# USB_to_SATA_bridge.net
KiCad netlist of a schematic drawn in Altium Designer
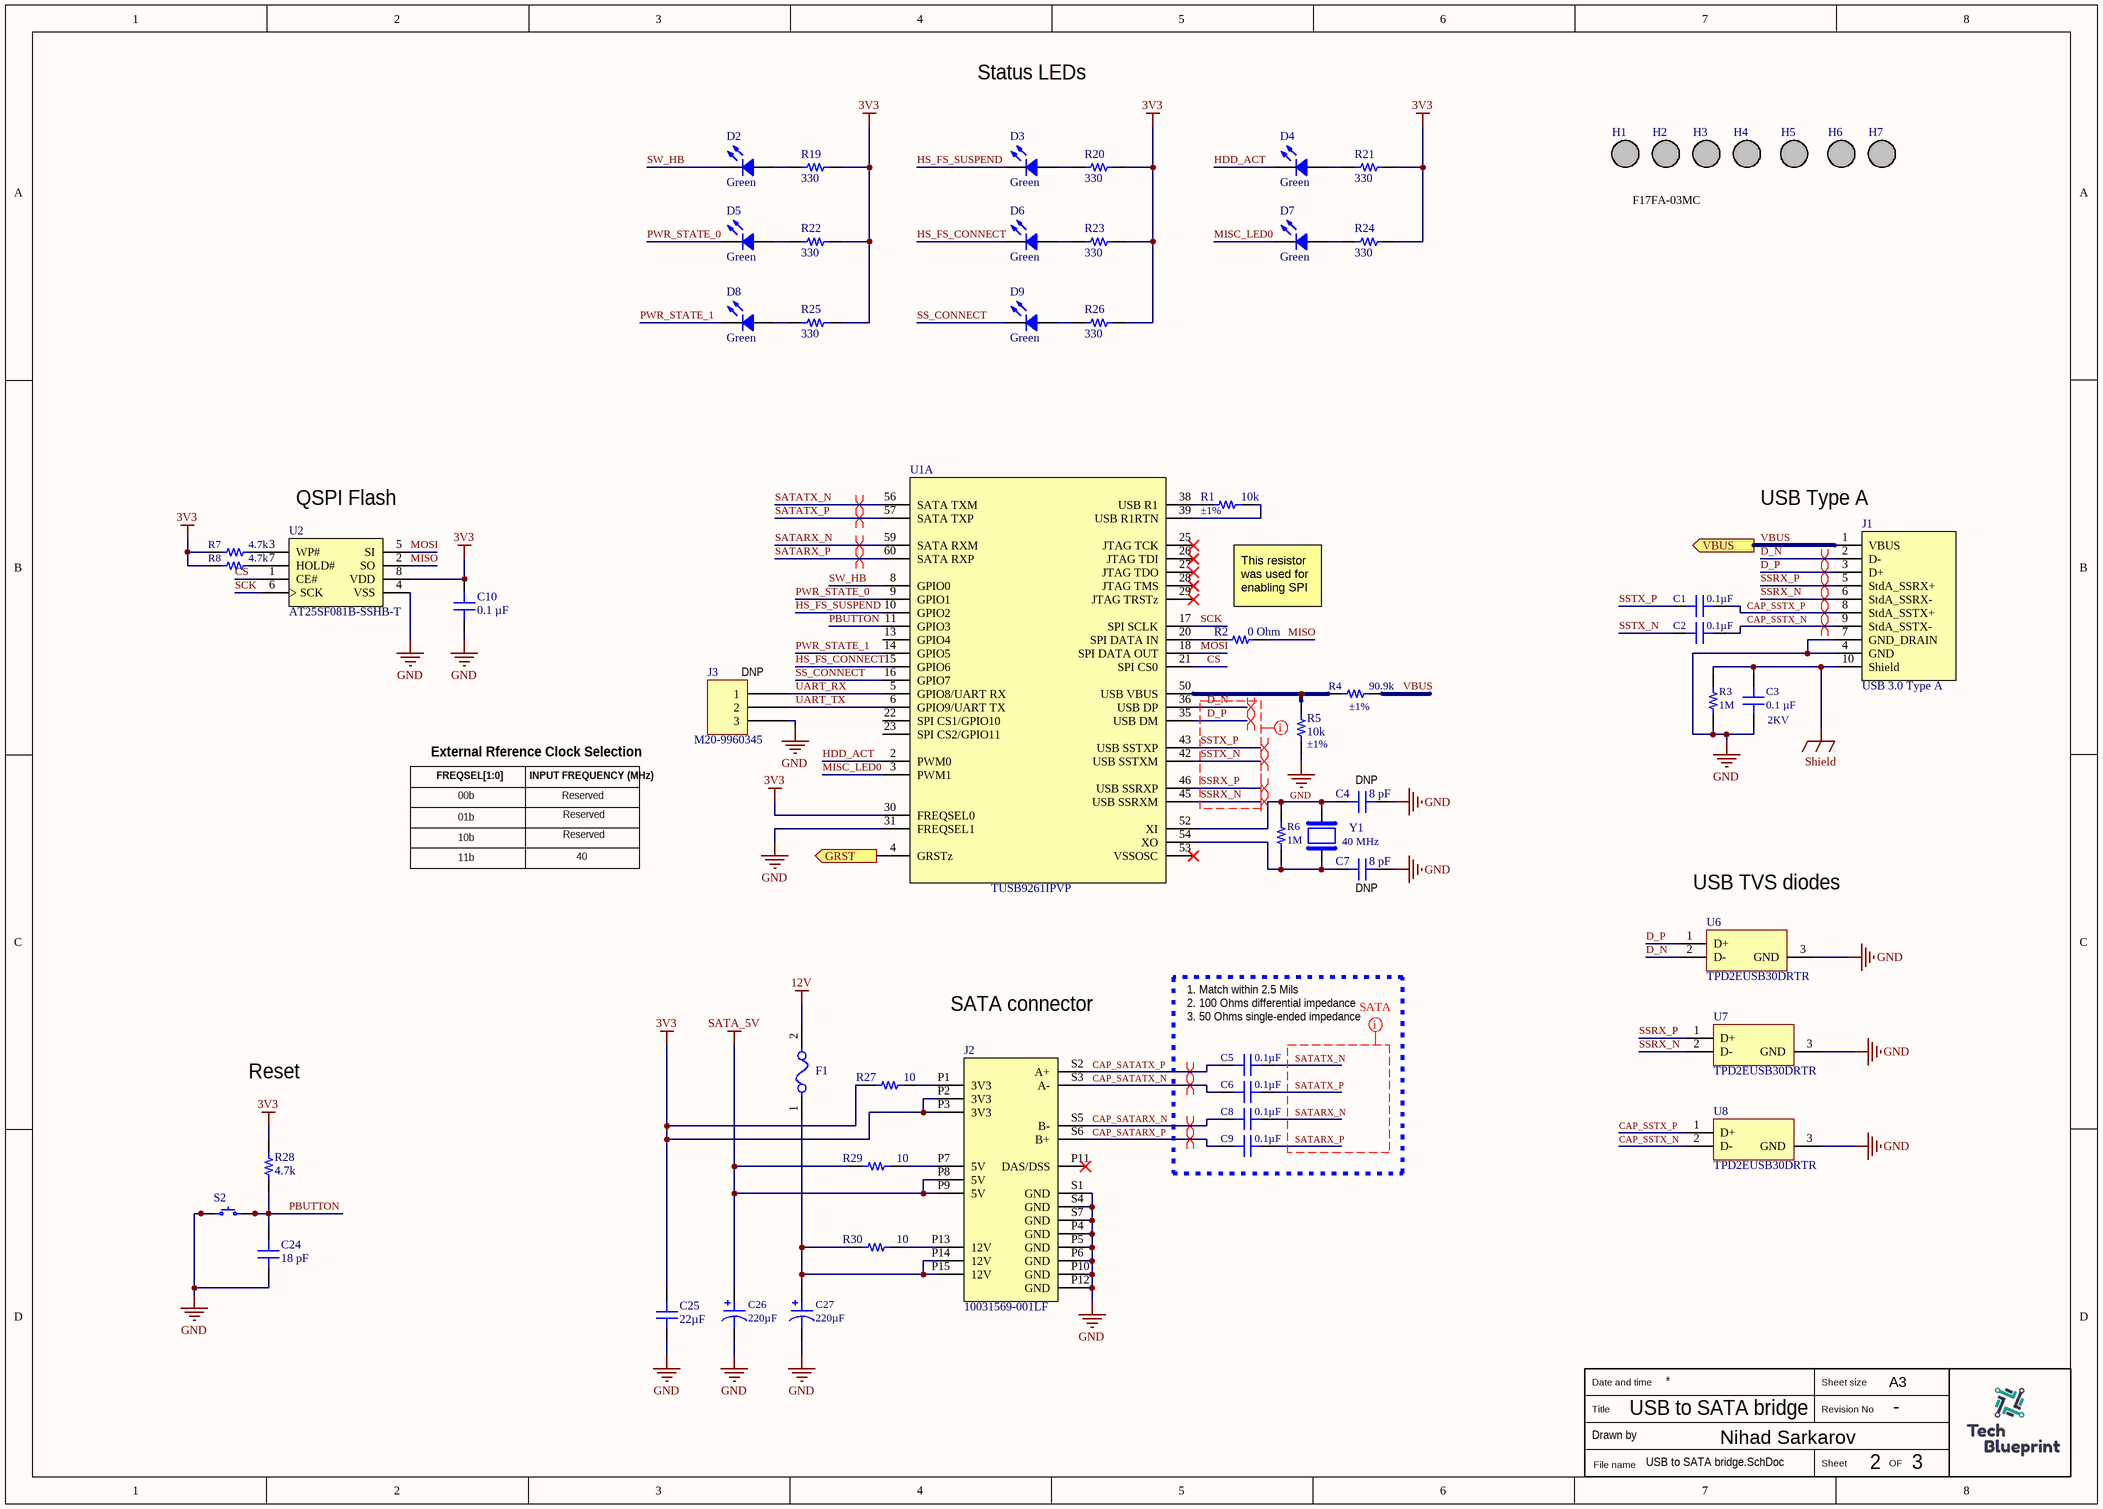
[diagram p0: USB to SATA bridge.SchDoc]

(export (version "E")
  (design (tool "Eeschema 10.0.6"))
  (components
    (comp (ref "C1")
      (value "0.1µF")
      (footprint "CAP 0402_1005")
      (description "CAP CER 0.1UF 16V X7R 0402")
      (fields
        (field (name "PART NUMBER") "0402YC104JAT4A")
        (field (name "CAPACITANCE") "0.1µF")
        (field (name "MANUFACTURER") "AVX Corporation")
      )
      (libsource (lib "Celestial Altium Library - altium_library") (part "Capacitor"))
    )
    (comp (ref "C2")
      (value "0.1µF")
      (footprint "CAP 0402_1005")
      (description "CAP CER 0.1UF 16V X7R 0402")
      (fields
        (field (name "PART NUMBER") "0402YC104JAT4A")
        (field (name "CAPACITANCE") "0.1µF")
        (field (name "MANUFACTURER") "AVX Corporation")
      )
      (libsource (lib "Celestial Altium Library - altium_library") (part "Capacitor"))
    )
    (comp (ref "C3")
      (value "0.1 µF")
      (footprint "MURATA GRM155 0402_1005")
      (description "CAP CER 0.1UF 100V X5R 0402")
      (fields
        (field (name "PART NUMBER") "GRM155R62A104ME14D")
        (field (name "CAPACITANCE") "0.1 µF")
        (field (name "MANUFACTURER") "Murata Electronics")
        (field (name "VOLTAGE - RATED") "2KV")
      )
      (libsource (lib "Celestial Altium Library - altium_library") (part "Capacitor"))
    )
    (comp (ref "C4")
      (value "8 pF")
      (footprint "MURATA GCM155 0402_1005")
      (description "CAP CER 8PF 50V C0G/NP0 0402")
      (fields
        (field (name "PART NUMBER") "GCM1555C1H8R0DA16D")
        (field (name "CAPACITANCE") "8 pF")
        (field (name "MANUFACTURER") "Murata Electronics")
      )
      (libsource (lib "Celestial Altium Library - altium_library") (part "Capacitor"))
    )
    (comp (ref "C5")
      (value "0.1µF")
      (footprint "CAP 0402_1005")
      (description "CAP CER 0.1UF 16V X7R 0402")
      (fields
        (field (name "PART NUMBER") "0402YC104JAT4A")
        (field (name "CAPACITANCE") "0.1µF")
        (field (name "MANUFACTURER") "AVX Corporation")
      )
      (libsource (lib "Celestial Altium Library - altium_library") (part "Capacitor"))
    )
    (comp (ref "C6")
      (value "0.1µF")
      (footprint "CAP 0402_1005")
      (description "CAP CER 0.1UF 16V X7R 0402")
      (fields
        (field (name "PART NUMBER") "0402YC104JAT4A")
        (field (name "CAPACITANCE") "0.1µF")
        (field (name "MANUFACTURER") "AVX Corporation")
      )
      (libsource (lib "Celestial Altium Library - altium_library") (part "Capacitor"))
    )
    (comp (ref "C7")
      (value "8 pF")
      (footprint "MURATA GCM155 0402_1005")
      (description "CAP CER 8PF 50V C0G/NP0 0402")
      (fields
        (field (name "PART NUMBER") "GCM1555C1H8R0DA16D")
        (field (name "CAPACITANCE") "8 pF")
        (field (name "MANUFACTURER") "Murata Electronics")
      )
      (libsource (lib "Celestial Altium Library - altium_library") (part "Capacitor"))
    )
    (comp (ref "C8")
      (value "0.1µF")
      (footprint "CAP 0402_1005")
      (description "CAP CER 0.1UF 16V X7R 0402")
      (fields
        (field (name "PART NUMBER") "0402YC104JAT4A")
        (field (name "CAPACITANCE") "0.1µF")
        (field (name "MANUFACTURER") "AVX Corporation")
      )
      (libsource (lib "Celestial Altium Library - altium_library") (part "Capacitor"))
    )
    (comp (ref "C9")
      (value "0.1µF")
      (footprint "CAP 0402_1005")
      (description "CAP CER 0.1UF 16V X7R 0402")
      (fields
        (field (name "PART NUMBER") "0402YC104JAT4A")
        (field (name "CAPACITANCE") "0.1µF")
        (field (name "MANUFACTURER") "AVX Corporation")
      )
      (libsource (lib "Celestial Altium Library - altium_library") (part "Capacitor"))
    )
    (comp (ref "C10")
      (value "0.1 µF")
      (footprint "CAP 0603_1608")
      (description "CAP CER 0.1UF 50V X7R 0603")
      (fields
        (field (name "PART NUMBER") "CL10B104KB85PND")
        (field (name "CAPACITANCE") "0.1 µF")
        (field (name "MANUFACTURER") "Samsung Electro-Mechanics")
      )
      (libsource (lib "Celestial Altium Library - altium_library") (part "Capacitor"))
    )
    (comp (ref "C24")
      (value "18 pF")
      (footprint "CAP 0402_1005")
      (description "CAP CER 18PF 50V C0G 0402")
      (fields
        (field (name "PART NUMBER") "CGA2B2C0G1H180J050BA")
        (field (name "CAPACITANCE") "18 pF")
        (field (name "MANUFACTURER") "TDK Corporation")
      )
      (libsource (lib "Celestial Altium Library - altium_library") (part "Capacitor"))
    )
    (comp (ref "C25")
      (value "22µF")
      (footprint "CAP 1206_3216 - 1.8MM")
      (description "CAP CER 22UF 16V X5R 1206")
      (fields
        (field (name "PART NUMBER") "1206YD226KAT2A")
        (field (name "CAPACITANCE") "22µF")
        (field (name "MANUFACTURER") "AVX Corporation")
      )
      (libsource (lib "Celestial Altium Library - altium_library") (part "Capacitor"))
    )
    (comp (ref "C26")
      (value "220µF")
      (footprint "CAP ALSMD 8.3MM H10.5MM")
      (description "CAP ALUM 220UF 20% 25V SMD")
      (fields (field (name "PART NUMBER") "UUR1E221MNL6GS") (field (name "MANUFACTURER") "Nichicon"))
      (libsource (lib "Celestial Altium Library - altium_library") (part "Polarised Capacitor"))
    )
    (comp (ref "C27")
      (value "220µF")
      (footprint "CAP ALSMD 8.3MM H10.5MM")
      (description "CAP ALUM 220UF 20% 25V SMD")
      (fields (field (name "PART NUMBER") "UUR1E221MNL6GS") (field (name "MANUFACTURER") "Nichicon"))
      (libsource (lib "Celestial Altium Library - altium_library") (part "Polarised Capacitor"))
    )
    (comp (ref "D2")
      (value "Green")
      (footprint "LED 0805_2012 GREEN")
      (description "0805 LED RED 570NM DOMINANT, 565")
      (fields
        (field (name "PART NUMBER") "QBLP631-YG1-2943")
        (field (name "MANUFACTURER") "QT Brightek (QTB)")
      )
      (libsource (lib "Celestial Altium Library - altium_library") (part "LED"))
    )
    (comp (ref "D3")
      (value "Green")
      (footprint "LED 0805_2012 GREEN")
      (description "0805 LED RED 570NM DOMINANT, 565")
      (fields
        (field (name "PART NUMBER") "QBLP631-YG1-2943")
        (field (name "MANUFACTURER") "QT Brightek (QTB)")
      )
      (libsource (lib "Celestial Altium Library - altium_library") (part "LED"))
    )
    (comp (ref "D4")
      (value "Green")
      (footprint "LED 0805_2012 GREEN")
      (description "0805 LED RED 570NM DOMINANT, 565")
      (fields
        (field (name "PART NUMBER") "QBLP631-YG1-2943")
        (field (name "MANUFACTURER") "QT Brightek (QTB)")
      )
      (libsource (lib "Celestial Altium Library - altium_library") (part "LED"))
    )
    (comp (ref "D5")
      (value "Green")
      (footprint "LED 0805_2012 GREEN")
      (description "0805 LED RED 570NM DOMINANT, 565")
      (fields
        (field (name "PART NUMBER") "QBLP631-YG1-2943")
        (field (name "MANUFACTURER") "QT Brightek (QTB)")
      )
      (libsource (lib "Celestial Altium Library - altium_library") (part "LED"))
    )
    (comp (ref "D6")
      (value "Green")
      (footprint "LED 0805_2012 GREEN")
      (description "0805 LED RED 570NM DOMINANT, 565")
      (fields
        (field (name "PART NUMBER") "QBLP631-YG1-2943")
        (field (name "MANUFACTURER") "QT Brightek (QTB)")
      )
      (libsource (lib "Celestial Altium Library - altium_library") (part "LED"))
    )
    (comp (ref "D7")
      (value "Green")
      (footprint "LED 0805_2012 GREEN")
      (description "0805 LED RED 570NM DOMINANT, 565")
      (fields
        (field (name "PART NUMBER") "QBLP631-YG1-2943")
        (field (name "MANUFACTURER") "QT Brightek (QTB)")
      )
      (libsource (lib "Celestial Altium Library - altium_library") (part "LED"))
    )
    (comp (ref "D8")
      (value "Green")
      (footprint "LED 0805_2012 GREEN")
      (description "0805 LED RED 570NM DOMINANT, 565")
      (fields
        (field (name "PART NUMBER") "QBLP631-YG1-2943")
        (field (name "MANUFACTURER") "QT Brightek (QTB)")
      )
      (libsource (lib "Celestial Altium Library - altium_library") (part "LED"))
    )
    (comp (ref "D9")
      (value "Green")
      (footprint "LED 0805_2012 GREEN")
      (description "0805 LED RED 570NM DOMINANT, 565")
      (fields
        (field (name "PART NUMBER") "QBLP631-YG1-2943")
        (field (name "MANUFACTURER") "QT Brightek (QTB)")
      )
      (libsource (lib "Celestial Altium Library - altium_library") (part "LED"))
    )
    (comp (ref "F1")
      (value "MINISMDC150F/24-2")
      (footprint "FP-MINISMDC150F-MFG")
      (description "PTC RESET FUSE 24V 1.5A 1812")
      (fields
        (field (name "MANUFACTURER") "Littelfuse")
        (field (name "OCTOPART") "https://octopart.com/minismdc150f%2F24-2-littelfuse-74215024")
      )
      (libsource (lib "Altium Content Vault") (part "5bcf9b9f640e542cf0359d10258e979"))
    )
    (comp (ref "H1") (value "Hole") (footprint "Hole") (libsource (lib "USB to SATA") (part "Hole")))
    (comp (ref "H2") (value "Hole") (footprint "Hole") (libsource (lib "USB to SATA") (part "Hole")))
    (comp (ref "H3") (value "Hole") (footprint "Hole") (libsource (lib "USB to SATA") (part "Hole")))
    (comp (ref "H4")
      (value "Mounting hole")
      (footprint "Mounting hole")
      (libsource (lib "USB to SATA") (part "Mounting hole"))
    )
    (comp (ref "H5")
      (value "Mounting hole")
      (footprint "Mounting hole")
      (libsource (lib "USB to SATA") (part "Mounting hole"))
    )
    (comp (ref "H6")
      (value "Mounting hole")
      (footprint "Mounting hole")
      (libsource (lib "USB to SATA") (part "Mounting hole"))
    )
    (comp (ref "H7")
      (value "Mounting hole")
      (footprint "Mounting hole")
      (libsource (lib "USB to SATA") (part "Mounting hole"))
    )
    (comp (ref "J1")
      (value "USB 3.0 Type A")
      (footprint "USB 3.0 Type A")
      (description "USB 3.0 Type A male connector")
      (libsource (lib "USB to SATA") (part "USB 3.0 Type A"))
    )
    (comp (ref "J2")
      (value "10031569-001LF")
      (footprint "AMPHENOL_10031569-001LF")
      (fields (field (name "MF") "{'manufacturer': u'Amphenol ICC'}"))
      (libsource (lib "USB to SATA") (part "10031569-001LF"))
    )
    (comp (ref "J3")
      (value "M20-9960345")
      (footprint "HARWIN M20-9960345")
      (description "CONN HEADER R/A 3POS 2.54MM")
      (fields (field (name "MANUFACTURER") "Harwin Inc."))
      (libsource (lib "Celestial Altium Library - altium_library") (part "3 Pin"))
    )
    (comp (ref "R1")
      (value "10k")
      (footprint "YAGEO RES 0402_1005")
      (description "RES 10K OHM 1% 1/5W 0402")
      (fields
        (field (name "PART NUMBER") "SR0402FR-7T10KL")
        (field (name "MANUFACTURER") "Yageo")
        (field (name "TOLERANCE") "±1%")
      )
      (libsource (lib "Celestial Altium Library - altium_library") (part "Resistor"))
    )
    (comp (ref "R2")
      (value "0 Ohm")
      (footprint "RES 0603_1608")
      (description "RCS0603 0R0 ET6 E3")
      (fields (field (name "PART NUMBER") "RCS06030000Z0EC") (field (name "MANUFACTURER") "Vishay Dale"))
      (libsource (lib "Celestial Altium Library - altium_library") (part "Resistor"))
    )
    (comp (ref "R3")
      (value "1M")
      (footprint "RES 0603_1608")
      (description "RES 1M OHM 5% 1/10W 0603")
      (fields
        (field (name "PART NUMBER") "RMCF0603JT1M00")
        (field (name "MANUFACTURER") "Stackpole Electronics Inc")
      )
      (libsource (lib "Celestial Altium Library - altium_library") (part "Resistor"))
    )
    (comp (ref "R4")
      (value "90.9k")
      (footprint "RES 0603_1608")
      (description "RES SMD 90.9K OHM 1% 1/8W 0603")
      (fields
        (field (name "PART NUMBER") "MCT06030C9092FP500")
        (field (name "MANUFACTURER") "Vishay Beyschlag")
        (field (name "TOLERANCE") "±1%")
      )
      (libsource (lib "Celestial Altium Library - altium_library") (part "Resistor"))
    )
    (comp (ref "R5")
      (value "10k")
      (footprint "YAGEO RES 0603_1608")
      (description "RES SMD 10K OHM 1% 1/10W 0603")
      (fields
        (field (name "PART NUMBER") "RT0603FRE0710KL")
        (field (name "MANUFACTURER") "Yageo")
        (field (name "TOLERANCE") "±1%")
      )
      (libsource (lib "Celestial Altium Library - altium_library") (part "Resistor"))
    )
    (comp (ref "R6")
      (value "1M")
      (footprint "YAGEO RES 0402_1005")
      (description "RES SMD 1M OHM 5% 1/16W 0402")
      (fields (field (name "PART NUMBER") "AC0402JR-071ML") (field (name "MANUFACTURER") "Yageo"))
      (libsource (lib "Celestial Altium Library - altium_library") (part "Resistor"))
    )
    (comp (ref "R7")
      (value "4.7k")
      (footprint "RES 0603_1608")
      (description "RES 4.7K OHM 5% 1/10W 0603")
      (fields
        (field (name "PART NUMBER") "RMCF0603JT4K70")
        (field (name "MANUFACTURER") "Stackpole Electronics Inc")
      )
      (libsource (lib "Celestial Altium Library - altium_library") (part "Resistor"))
    )
    (comp (ref "R8")
      (value "4.7k")
      (footprint "RES 0603_1608")
      (description "RES 4.7K OHM 5% 1/10W 0603")
      (fields
        (field (name "PART NUMBER") "RMCF0603JT4K70")
        (field (name "MANUFACTURER") "Stackpole Electronics Inc")
      )
      (libsource (lib "Celestial Altium Library - altium_library") (part "Resistor"))
    )
    (comp (ref "R19")
      (value "330")
      (footprint "YAGEO RES 0402_1005")
      (description "RES SMD 330 OHM 5% 1/16W 0402")
      (fields (field (name "PART NUMBER") "AC0402JR-07330RL") (field (name "MANUFACTURER") "Yageo"))
      (libsource (lib "Celestial Altium Library - altium_library") (part "Resistor"))
    )
    (comp (ref "R20")
      (value "330")
      (footprint "YAGEO RES 0402_1005")
      (description "RES SMD 330 OHM 5% 1/16W 0402")
      (fields (field (name "PART NUMBER") "AC0402JR-07330RL") (field (name "MANUFACTURER") "Yageo"))
      (libsource (lib "Celestial Altium Library - altium_library") (part "Resistor"))
    )
    (comp (ref "R21")
      (value "330")
      (footprint "YAGEO RES 0402_1005")
      (description "RES SMD 330 OHM 5% 1/16W 0402")
      (fields (field (name "PART NUMBER") "AC0402JR-07330RL") (field (name "MANUFACTURER") "Yageo"))
      (libsource (lib "Celestial Altium Library - altium_library") (part "Resistor"))
    )
    (comp (ref "R22")
      (value "330")
      (footprint "YAGEO RES 0402_1005")
      (description "RES SMD 330 OHM 5% 1/16W 0402")
      (fields (field (name "PART NUMBER") "AC0402JR-07330RL") (field (name "MANUFACTURER") "Yageo"))
      (libsource (lib "Celestial Altium Library - altium_library") (part "Resistor"))
    )
    (comp (ref "R23")
      (value "330")
      (footprint "YAGEO RES 0402_1005")
      (description "RES SMD 330 OHM 5% 1/16W 0402")
      (fields (field (name "PART NUMBER") "AC0402JR-07330RL") (field (name "MANUFACTURER") "Yageo"))
      (libsource (lib "Celestial Altium Library - altium_library") (part "Resistor"))
    )
    (comp (ref "R24")
      (value "330")
      (footprint "YAGEO RES 0402_1005")
      (description "RES SMD 330 OHM 5% 1/16W 0402")
      (fields (field (name "PART NUMBER") "AC0402JR-07330RL") (field (name "MANUFACTURER") "Yageo"))
      (libsource (lib "Celestial Altium Library - altium_library") (part "Resistor"))
    )
    (comp (ref "R25")
      (value "330")
      (footprint "YAGEO RES 0402_1005")
      (description "RES SMD 330 OHM 5% 1/16W 0402")
      (fields (field (name "PART NUMBER") "AC0402JR-07330RL") (field (name "MANUFACTURER") "Yageo"))
      (libsource (lib "Celestial Altium Library - altium_library") (part "Resistor"))
    )
    (comp (ref "R26")
      (value "330")
      (footprint "YAGEO RES 0402_1005")
      (description "RES SMD 330 OHM 5% 1/16W 0402")
      (fields (field (name "PART NUMBER") "AC0402JR-07330RL") (field (name "MANUFACTURER") "Yageo"))
      (libsource (lib "Celestial Altium Library - altium_library") (part "Resistor"))
    )
    (comp (ref "R27")
      (value "10")
      (footprint "RES 1206_3216")
      (description "RCC1206 200 10R 5% ET1 E3")
      (fields (field (name "PART NUMBER") "RCC120610R0JNEA") (field (name "MANUFACTURER") "Vishay Dale"))
      (libsource (lib "Celestial Altium Library - altium_library") (part "Resistor"))
    )
    (comp (ref "R28")
      (value "4.7k")
      (footprint "YAGEO RES 0402_1005")
      (description "RES SMD 4.7K OHM 5% 1/16W 0402")
      (fields (field (name "PART NUMBER") "AC0402JR-074K7L") (field (name "MANUFACTURER") "Yageo"))
      (libsource (lib "Celestial Altium Library - altium_library") (part "Resistor"))
    )
    (comp (ref "R29")
      (value "10")
      (footprint "RES 1206_3216")
      (description "RCC1206 200 10R 5% ET1 E3")
      (fields (field (name "PART NUMBER") "RCC120610R0JNEA") (field (name "MANUFACTURER") "Vishay Dale"))
      (libsource (lib "Celestial Altium Library - altium_library") (part "Resistor"))
    )
    (comp (ref "R30")
      (value "10")
      (footprint "RES 1206_3216")
      (description "RCC1206 200 10R 5% ET1 E3")
      (fields (field (name "PART NUMBER") "RCC120610R0JNEA") (field (name "MANUFACTURER") "Vishay Dale"))
      (libsource (lib "Celestial Altium Library - altium_library") (part "Resistor"))
    )
    (comp (ref "S2")
      (value "PTS645SM43SMTR92 LFS")
      (footprint "C&K PTS645")
      (description "SWITCH TACTILE SPST-NO 0.05A 12V")
      (fields (field (name "MANUFACTURER") "C&K"))
      (libsource (lib "Celestial Altium Library - altium_library") (part "SPST-NO 4 PIN"))
    )
    (comp (ref "U1")
      (value "TUSB9261IPVP")
      (footprint "FP-PVP0064A-IPC_A")
      (description "HDD, CD, DVD Drive Interface 64-HTQFP (7x7)")
      (fields
        (field (name "MANUFACTURER") "Texas Instruments")
        (field (name "DIGIKEY PART NUMBER") "296-35545-ND")
      )
      (libsource (lib "USB to SATA") (part "TUSB9261IPVP"))
    )
    (comp (ref "U2")
      (value "AT25SF081B-SSHB-T")
      (footprint "SST25VF016B-75-4I-S2AF-T:SOIC127P790X216-8N")
      (description "FLASH - NOR Memory IC 8Mbit SPI - Quad I/O 108 MHz 8-SOIC")
      (fields
        (field (name "MF") "{'manufacturer': u'Microchip Technology'}")
        (field (name "MP") "SST25VF016B-75-4I-S2AF-T")
      )
      (libsource (lib "USB to SATA") (part "SST25VF016B-75-4I-S2AF-T"))
    )
    (comp (ref "U6")
      (value "TPD2EUSB30DRTR")
      (footprint "DRT0003A")
      (fields (field (name "MANUFACTURER") "Texas Instruments"))
      (libsource (lib "Altium Content Vault") (part "TI-TPD2EUSB30-SOT_DRT-3"))
    )
    (comp (ref "U7")
      (value "TPD2EUSB30DRTR")
      (footprint "DRT0003A")
      (fields (field (name "MANUFACTURER") "Texas Instruments"))
      (libsource (lib "Altium Content Vault") (part "TI-TPD2EUSB30-SOT_DRT-3"))
    )
    (comp (ref "U8")
      (value "TPD2EUSB30DRTR")
      (footprint "DRT0003A")
      (fields (field (name "MANUFACTURER") "Texas Instruments"))
      (libsource (lib "Altium Content Vault") (part "TI-TPD2EUSB30-SOT_DRT-3"))
    )
    (comp (ref "Y1")
      (value "SXT22412AA07-40.000M")
      (footprint "XTAL_SXT22412AA16-40.000MT")
      (description "40 MHz ±50ppm Crystal 12pF 50 Ohms 4-SMD, No Lead")
      (fields (field (name "MF") "Suntsu Electronics, Inc") (field (name "FREQUENCY") "40 MHz"))
      (libsource (lib "USB to SATA") (part "SXT22412AA07-40.000M"))
    )
  )
  (nets
    (net (code "1") (name "/CAP_SATARX_N") (class "Default")
      (node (ref "C8") (pin "1") (pinfunction "1_1") (pintype "passive"))
      (node (ref "J2") (pin "S5") (pinfunction "B-_S5") (pintype "passive"))
    )
    (net (code "2") (name "/CAP_SATARX_P") (class "Default")
      (node (ref "C9") (pin "1") (pinfunction "1_1") (pintype "passive"))
      (node (ref "J2") (pin "S6") (pinfunction "B+_S6") (pintype "passive"))
    )
    (net (code "3") (name "/CAP_SATATX_N") (class "Default")
      (node (ref "C6") (pin "1") (pinfunction "1_1") (pintype "passive"))
      (node (ref "J2") (pin "S3") (pinfunction "A-_S3") (pintype "passive"))
    )
    (net (code "4") (name "/CAP_SATATX_P") (class "Default")
      (node (ref "C5") (pin "1") (pinfunction "1_1") (pintype "passive"))
      (node (ref "J2") (pin "S2") (pinfunction "A+_S2") (pintype "passive"))
    )
    (net (code "5") (name "/CAP_SSTX_N") (class "Default")
      (node (ref "C2") (pin "2") (pinfunction "2_2") (pintype "passive"))
      (node (ref "J1") (pin "9") (pinfunction "StdA_SSTX-_9") (pintype "passive"))
      (node (ref "U8") (pin "2") (pinfunction "D-_2") (pintype "passive"))
    )
    (net (code "6") (name "/CAP_SSTX_P") (class "Default")
      (node (ref "C1") (pin "2") (pinfunction "2_2") (pintype "passive"))
      (node (ref "J1") (pin "8") (pinfunction "StdA_SSTX+_8") (pintype "passive"))
      (node (ref "U8") (pin "1") (pinfunction "D+_1") (pintype "passive"))
    )
    (net (code "7") (name "/CS") (class "Default")
      (node (ref "U1") (pin "21") (pinfunction "SPI_CS0_21") (pintype "passive"))
      (node (ref "U2") (pin "1") (pinfunction "CE#_1") (pintype "passive"))
    )
    (net (code "8") (name "/D_N") (class "Default")
      (node (ref "J1") (pin "2") (pinfunction "D-_2") (pintype "passive"))
      (node (ref "U1") (pin "36") (pinfunction "USB_DP_36") (pintype "passive"))
      (node (ref "U6") (pin "2") (pinfunction "D-_2") (pintype "passive"))
    )
    (net (code "9") (name "/D_P") (class "Default")
      (node (ref "J1") (pin "3") (pinfunction "D+_3") (pintype "passive"))
      (node (ref "U1") (pin "35") (pinfunction "USB_DM_35") (pintype "passive"))
      (node (ref "U6") (pin "1") (pinfunction "D+_1") (pintype "passive"))
    )
    (net (code "10") (name "/GRST") (class "Default")
      (node (ref "U1") (pin "4") (pinfunction "GRSTz_4") (pintype "passive"))
    )
    (net (code "11") (name "/HDD_ACT") (class "Default")
      (node (ref "D4") (pin "2") (pinfunction "2_2") (pintype "passive"))
      (node (ref "U1") (pin "2") (pinfunction "PWM0_2") (pintype "passive"))
    )
    (net (code "12") (name "/HS_FS_CONNECT") (class "Default")
      (node (ref "D6") (pin "2") (pinfunction "2_2") (pintype "passive"))
      (node (ref "U1") (pin "15") (pinfunction "GPIO6_15") (pintype "passive"))
    )
    (net (code "13") (name "/HS_FS_SUSPEND") (class "Default")
      (node (ref "D3") (pin "2") (pinfunction "2_2") (pintype "passive"))
      (node (ref "U1") (pin "10") (pinfunction "GPIO2_10") (pintype "passive"))
    )
    (net (code "14") (name "/MISC_LED0") (class "Default")
      (node (ref "D7") (pin "2") (pinfunction "2_2") (pintype "passive"))
      (node (ref "U1") (pin "3") (pinfunction "PWM1_3") (pintype "passive"))
    )
    (net (code "15") (name "/MISO") (class "Default")
      (node (ref "R2") (pin "2") (pinfunction "2_2") (pintype "passive"))
      (node (ref "U2") (pin "2") (pinfunction "SO_2") (pintype "passive"))
    )
    (net (code "16") (name "/MOSI") (class "Default")
      (node (ref "U1") (pin "18") (pinfunction "SPI_DATA_OUT_18") (pintype "passive"))
      (node (ref "U2") (pin "5") (pinfunction "SI_5") (pintype "passive"))
    )
    (net (code "17") (name "/PBUTTON") (class "Default")
      (node (ref "C24") (pin "2") (pinfunction "2_2") (pintype "passive"))
      (node (ref "R28") (pin "1") (pinfunction "1_1") (pintype "passive"))
      (node (ref "S2") (pin "3") (pinfunction "3_3") (pintype "passive"))
      (node (ref "S2") (pin "4") (pinfunction "4_4") (pintype "passive"))
      (node (ref "U1") (pin "11") (pinfunction "GPIO3_11") (pintype "passive"))
    )
    (net (code "18") (name "/PWR_STATE_0") (class "Default")
      (node (ref "D5") (pin "2") (pinfunction "2_2") (pintype "passive"))
      (node (ref "U1") (pin "9") (pinfunction "GPIO1_9") (pintype "passive"))
    )
    (net (code "19") (name "/PWR_STATE_1") (class "Default")
      (node (ref "D8") (pin "2") (pinfunction "2_2") (pintype "passive"))
      (node (ref "U1") (pin "14") (pinfunction "GPIO5_14") (pintype "passive"))
    )
    (net (code "20") (name "/SATARX_N") (class "Default")
      (node (ref "C8") (pin "2") (pinfunction "2_2") (pintype "passive"))
      (node (ref "U1") (pin "59") (pinfunction "SATA_RXM_59") (pintype "passive"))
    )
    (net (code "21") (name "/SATARX_P") (class "Default")
      (node (ref "C9") (pin "2") (pinfunction "2_2") (pintype "passive"))
      (node (ref "U1") (pin "60") (pinfunction "SATA_RXP_60") (pintype "passive"))
    )
    (net (code "22") (name "/SATATX_N") (class "Default")
      (node (ref "C5") (pin "2") (pinfunction "2_2") (pintype "passive"))
      (node (ref "U1") (pin "56") (pinfunction "SATA_TXM_56") (pintype "passive"))
    )
    (net (code "23") (name "/SATATX_P") (class "Default")
      (node (ref "C6") (pin "2") (pinfunction "2_2") (pintype "passive"))
      (node (ref "U1") (pin "57") (pinfunction "SATA_TXP_57") (pintype "passive"))
    )
    (net (code "24") (name "/SCK") (class "Default")
      (node (ref "U1") (pin "17") (pinfunction "SPI_SCLK_17") (pintype "passive"))
      (node (ref "U2") (pin "6") (pinfunction "SCK_6") (pintype "passive"))
    )
    (net (code "25") (name "/SSRX_N") (class "Default")
      (node (ref "J1") (pin "6") (pinfunction "StdA_SSRX-_6") (pintype "passive"))
      (node (ref "U1") (pin "45") (pinfunction "USB_SSRXM_45") (pintype "passive"))
      (node (ref "U7") (pin "2") (pinfunction "D-_2") (pintype "passive"))
    )
    (net (code "26") (name "/SSRX_P") (class "Default")
      (node (ref "J1") (pin "5") (pinfunction "StdA_SSRX+_5") (pintype "passive"))
      (node (ref "U1") (pin "46") (pinfunction "USB_SSRXP_46") (pintype "passive"))
      (node (ref "U7") (pin "1") (pinfunction "D+_1") (pintype "passive"))
    )
    (net (code "27") (name "/SSTX_N") (class "Default")
      (node (ref "C2") (pin "1") (pinfunction "1_1") (pintype "passive"))
      (node (ref "U1") (pin "42") (pinfunction "USB_SSTXM_42") (pintype "passive"))
    )
    (net (code "28") (name "/SSTX_P") (class "Default")
      (node (ref "C1") (pin "1") (pinfunction "1_1") (pintype "passive"))
      (node (ref "U1") (pin "43") (pinfunction "USB_SSTXP_43") (pintype "passive"))
    )
    (net (code "29") (name "/SS_CONNECT") (class "Default")
      (node (ref "D9") (pin "2") (pinfunction "2_2") (pintype "passive"))
      (node (ref "U1") (pin "16") (pinfunction "GPIO7_16") (pintype "passive"))
    )
    (net (code "30") (name "/SW_HB") (class "Default")
      (node (ref "D2") (pin "2") (pinfunction "2_2") (pintype "passive"))
      (node (ref "U1") (pin "8") (pinfunction "GPIO0_8") (pintype "passive"))
    )
    (net (code "31") (name "/UART_RX") (class "Default")
      (node (ref "J3") (pin "1") (pinfunction "1_1") (pintype "passive"))
      (node (ref "U1") (pin "5") (pinfunction "GPIO8/UART_RX_5") (pintype "passive"))
    )
    (net (code "32") (name "/UART_TX") (class "Default")
      (node (ref "J3") (pin "2") (pinfunction "2_2") (pintype "passive"))
      (node (ref "U1") (pin "6") (pinfunction "GPIO9/UART_TX_6") (pintype "passive"))
    )
    (net (code "33") (name "/VBUS") (class "Default")
      (node (ref "J1") (pin "1") (pinfunction "VBUS_1") (pintype "passive"))
      (node (ref "R4") (pin "2") (pinfunction "2_2") (pintype "passive"))
    )
    (net (code "34") (name "3V3") (class "Default")
      (node (ref "C10") (pin "2") (pinfunction "2_2") (pintype "passive"))
      (node (ref "C25") (pin "2") (pinfunction "2_2") (pintype "passive"))
      (node (ref "J2") (pin "P2") (pinfunction "3V3_P2") (pintype "passive"))
      (node (ref "J2") (pin "P3") (pinfunction "3V3_P3") (pintype "passive"))
      (node (ref "R19") (pin "2") (pinfunction "2_2") (pintype "passive"))
      (node (ref "R20") (pin "2") (pinfunction "2_2") (pintype "passive"))
      (node (ref "R21") (pin "2") (pinfunction "2_2") (pintype "passive"))
      (node (ref "R22") (pin "2") (pinfunction "2_2") (pintype "passive"))
      (node (ref "R23") (pin "2") (pinfunction "2_2") (pintype "passive"))
      (node (ref "R24") (pin "2") (pinfunction "2_2") (pintype "passive"))
      (node (ref "R25") (pin "2") (pinfunction "2_2") (pintype "passive"))
      (node (ref "R26") (pin "2") (pinfunction "2_2") (pintype "passive"))
      (node (ref "R27") (pin "1") (pinfunction "1_1") (pintype "passive"))
      (node (ref "R28") (pin "2") (pinfunction "2_2") (pintype "passive"))
      (node (ref "R7") (pin "1") (pinfunction "1_1") (pintype "passive"))
      (node (ref "R8") (pin "1") (pinfunction "1_1") (pintype "passive"))
      (node (ref "U1") (pin "30") (pinfunction "FREQSEL0_30") (pintype "passive"))
      (node (ref "U2") (pin "8") (pinfunction "VDD_8") (pintype "power_in"))
    )
    (net (code "35") (name "12V") (class "Default")
      (node (ref "F1") (pin "2") (pinfunction "2_2") (pintype "passive"))
    )
    (net (code "36") (name "GND") (class "Default")
      (node (ref "C10") (pin "1") (pinfunction "1_1") (pintype "passive"))
      (node (ref "C24") (pin "1") (pinfunction "1_1") (pintype "passive"))
      (node (ref "C25") (pin "1") (pinfunction "1_1") (pintype "passive"))
      (node (ref "C26") (pin "2") (pinfunction "2_2") (pintype "passive"))
      (node (ref "C27") (pin "2") (pinfunction "2_2") (pintype "passive"))
      (node (ref "C3") (pin "1") (pinfunction "1_1") (pintype "passive"))
      (node (ref "C4") (pin "2") (pinfunction "2_2") (pintype "passive"))
      (node (ref "C7") (pin "2") (pinfunction "2_2") (pintype "passive"))
      (node (ref "J1") (pin "4") (pinfunction "GND_4") (pintype "passive"))
      (node (ref "J1") (pin "7") (pinfunction "GND_DRAIN_7") (pintype "passive"))
      (node (ref "J2") (pin "P10") (pinfunction "GND_P10") (pintype "passive"))
      (node (ref "J2") (pin "P12") (pinfunction "GND_P12") (pintype "passive"))
      (node (ref "J2") (pin "P4") (pinfunction "GND_P4") (pintype "passive"))
      (node (ref "J2") (pin "P5") (pinfunction "GND_P5") (pintype "passive"))
      (node (ref "J2") (pin "P6") (pinfunction "GND_P6") (pintype "passive"))
      (node (ref "J2") (pin "S1") (pinfunction "GND_S1") (pintype "passive"))
      (node (ref "J2") (pin "S4") (pinfunction "GND_S4") (pintype "passive"))
      (node (ref "J2") (pin "S7") (pinfunction "GND_S7") (pintype "passive"))
      (node (ref "J3") (pin "3") (pinfunction "3_3") (pintype "passive"))
      (node (ref "R3") (pin "1") (pinfunction "1_1") (pintype "passive"))
      (node (ref "R5") (pin "1") (pinfunction "1_1") (pintype "passive"))
      (node (ref "S2") (pin "1") (pinfunction "1_1") (pintype "passive"))
      (node (ref "S2") (pin "2") (pinfunction "2_2") (pintype "passive"))
      (node (ref "U1") (pin "31") (pinfunction "FREQSEL1_31") (pintype "passive"))
      (node (ref "U2") (pin "4") (pinfunction "VSS_4") (pintype "power_in"))
      (node (ref "U6") (pin "3") (pinfunction "GND_3") (pintype "power_in"))
      (node (ref "U7") (pin "3") (pinfunction "GND_3") (pintype "power_in"))
      (node (ref "U8") (pin "3") (pinfunction "GND_3") (pintype "power_in"))
    )
    (net (code "37") (name "Net-(C27-Pad1)") (class "Default")
      (node (ref "C27") (pin "1") (pinfunction "1_1") (pintype "passive"))
      (node (ref "F1") (pin "1") (pinfunction "1_1") (pintype "passive"))
      (node (ref "J2") (pin "P14") (pinfunction "12V_P14") (pintype "passive"))
      (node (ref "J2") (pin "P15") (pinfunction "12V_P15") (pintype "passive"))
      (node (ref "R30") (pin "1") (pinfunction "1_1") (pintype "passive"))
    )
    (net (code "38") (name "Net-(D2-Pad1)") (class "Default")
      (node (ref "D2") (pin "1") (pinfunction "1_1") (pintype "passive"))
      (node (ref "R19") (pin "1") (pinfunction "1_1") (pintype "passive"))
    )
    (net (code "39") (name "Net-(D3-Pad1)") (class "Default")
      (node (ref "D3") (pin "1") (pinfunction "1_1") (pintype "passive"))
      (node (ref "R20") (pin "1") (pinfunction "1_1") (pintype "passive"))
    )
    (net (code "40") (name "Net-(D4-Pad1)") (class "Default")
      (node (ref "D4") (pin "1") (pinfunction "1_1") (pintype "passive"))
      (node (ref "R21") (pin "1") (pinfunction "1_1") (pintype "passive"))
    )
    (net (code "41") (name "Net-(D5-Pad1)") (class "Default")
      (node (ref "D5") (pin "1") (pinfunction "1_1") (pintype "passive"))
      (node (ref "R22") (pin "1") (pinfunction "1_1") (pintype "passive"))
    )
    (net (code "42") (name "Net-(D6-Pad1)") (class "Default")
      (node (ref "D6") (pin "1") (pinfunction "1_1") (pintype "passive"))
      (node (ref "R23") (pin "1") (pinfunction "1_1") (pintype "passive"))
    )
    (net (code "43") (name "Net-(D7-Pad1)") (class "Default")
      (node (ref "D7") (pin "1") (pinfunction "1_1") (pintype "passive"))
      (node (ref "R24") (pin "1") (pinfunction "1_1") (pintype "passive"))
    )
    (net (code "44") (name "Net-(D8-Pad1)") (class "Default")
      (node (ref "D8") (pin "1") (pinfunction "1_1") (pintype "passive"))
      (node (ref "R25") (pin "1") (pinfunction "1_1") (pintype "passive"))
    )
    (net (code "45") (name "Net-(D9-Pad1)") (class "Default")
      (node (ref "D9") (pin "1") (pinfunction "1_1") (pintype "passive"))
      (node (ref "R26") (pin "1") (pinfunction "1_1") (pintype "passive"))
    )
    (net (code "46") (name "Net-(J2-3V3-PadP1)") (class "Default")
      (node (ref "J2") (pin "P1") (pinfunction "3V3_P1") (pintype "passive"))
      (node (ref "R27") (pin "2") (pinfunction "2_2") (pintype "passive"))
    )
    (net (code "47") (name "Net-(J2-5V-PadP7)") (class "Default")
      (node (ref "J2") (pin "P7") (pinfunction "5V_P7") (pintype "passive"))
      (node (ref "R29") (pin "2") (pinfunction "2_2") (pintype "passive"))
    )
    (net (code "48") (name "Net-(J2-12V-PadP13)") (class "Default")
      (node (ref "J2") (pin "P13") (pinfunction "12V_P13") (pintype "passive"))
      (node (ref "R30") (pin "2") (pinfunction "2_2") (pintype "passive"))
    )
    (net (code "49") (name "Net-(U1A-SPI_DATA_IN)") (class "Default")
      (node (ref "R2") (pin "1") (pinfunction "1_1") (pintype "passive"))
      (node (ref "U1") (pin "20") (pinfunction "SPI_DATA_IN_20") (pintype "passive"))
    )
    (net (code "50") (name "Net-(U1A-USB_R1)") (class "Default")
      (node (ref "R1") (pin "1") (pinfunction "1_1") (pintype "passive"))
      (node (ref "U1") (pin "38") (pinfunction "USB_R1_38") (pintype "passive"))
    )
    (net (code "51") (name "Net-(U1A-USB_R1RTN)") (class "Default")
      (node (ref "R1") (pin "2") (pinfunction "2_2") (pintype "passive"))
      (node (ref "U1") (pin "39") (pinfunction "USB_R1RTN_39") (pintype "passive"))
    )
    (net (code "52") (name "Net-(U1A-USB_VBUS)") (class "Default")
      (node (ref "R4") (pin "1") (pinfunction "1_1") (pintype "passive"))
      (node (ref "R5") (pin "2") (pinfunction "2_2") (pintype "passive"))
      (node (ref "U1") (pin "50") (pinfunction "USB_VBUS_50") (pintype "passive"))
    )
    (net (code "53") (name "Net-(U1A-XI)") (class "Default")
      (node (ref "C4") (pin "1") (pinfunction "1_1") (pintype "passive"))
      (node (ref "R6") (pin "2") (pinfunction "2_2") (pintype "passive"))
      (node (ref "U1") (pin "52") (pinfunction "XI_52") (pintype "passive"))
      (node (ref "Y1") (pin "3") (pinfunction "3_3") (pintype "passive"))
    )
    (net (code "54") (name "Net-(U1A-XO)") (class "Default")
      (node (ref "C7") (pin "1") (pinfunction "1_1") (pintype "passive"))
      (node (ref "R6") (pin "1") (pinfunction "1_1") (pintype "passive"))
      (node (ref "U1") (pin "54") (pinfunction "XO_54") (pintype "passive"))
      (node (ref "Y1") (pin "1") (pinfunction "1_1") (pintype "passive"))
    )
    (net (code "55") (name "Net-(U2-HOLD#)") (class "Default")
      (node (ref "R8") (pin "2") (pinfunction "2_2") (pintype "passive"))
      (node (ref "U2") (pin "7") (pinfunction "HOLD#_7") (pintype "passive"))
    )
    (net (code "56") (name "Net-(U2-WP#)") (class "Default")
      (node (ref "R7") (pin "2") (pinfunction "2_2") (pintype "passive"))
      (node (ref "U2") (pin "3") (pinfunction "WP#_3") (pintype "passive"))
    )
    (net (code "57") (name "SATA_5V") (class "Default")
      (node (ref "C26") (pin "1") (pinfunction "1_1") (pintype "passive"))
      (node (ref "J2") (pin "P8") (pinfunction "5V_P8") (pintype "passive"))
      (node (ref "J2") (pin "P9") (pinfunction "5V_P9") (pintype "passive"))
      (node (ref "R29") (pin "1") (pinfunction "1_1") (pintype "passive"))
    )
    (net (code "58") (name "Shield") (class "Default")
      (node (ref "C3") (pin "2") (pinfunction "2_2") (pintype "passive"))
      (node (ref "J1") (pin "10") (pinfunction "Shield_10") (pintype "passive"))
      (node (ref "R3") (pin "2") (pinfunction "2_2") (pintype "passive"))
    )
    (net (code "59") (name "unconnected-(J2-DAS{slash}DSS-PadP11)") (class "Default")
      (node (ref "J2") (pin "P11") (pinfunction "DAS/DSS_P11") (pintype "passive+no_connect"))
    )
    (net (code "60") (name "unconnected-(U1A-GPIO4-Pad13)") (class "Default")
      (node (ref "U1") (pin "13") (pinfunction "GPIO4_13") (pintype "passive"))
    )
    (net (code "61") (name "unconnected-(U1A-JTAG_TCK-Pad25)") (class "Default")
      (node (ref "U1") (pin "25") (pinfunction "JTAG_TCK_25") (pintype "passive+no_connect"))
    )
    (net (code "62") (name "unconnected-(U1A-JTAG_TDI-Pad26)") (class "Default")
      (node (ref "U1") (pin "26") (pinfunction "JTAG_TDI_26") (pintype "passive+no_connect"))
    )
    (net (code "63") (name "unconnected-(U1A-JTAG_TDO-Pad27)") (class "Default")
      (node (ref "U1") (pin "27") (pinfunction "JTAG_TDO_27") (pintype "passive+no_connect"))
    )
    (net (code "64") (name "unconnected-(U1A-JTAG_TMS-Pad28)") (class "Default")
      (node (ref "U1") (pin "28") (pinfunction "JTAG_TMS_28") (pintype "passive+no_connect"))
    )
    (net (code "65") (name "unconnected-(U1A-JTAG_TRSTz-Pad29)") (class "Default")
      (node (ref "U1") (pin "29") (pinfunction "JTAG_TRSTz_29") (pintype "passive+no_connect"))
    )
    (net (code "66") (name "unconnected-(U1A-SPI_CS1{slash}GPIO10-Pad22)") (class "Default")
      (node (ref "U1") (pin "22") (pinfunction "SPI_CS1/GPIO10_22") (pintype "passive"))
    )
    (net (code "67") (name "unconnected-(U1A-SPI_CS2{slash}GPIO11-Pad23)") (class "Default")
      (node (ref "U1") (pin "23") (pinfunction "SPI_CS2/GPIO11_23") (pintype "passive"))
    )
    (net (code "68") (name "unconnected-(U1A-VSSOSC-Pad53)") (class "Default")
      (node (ref "U1") (pin "53") (pinfunction "VSSOSC_53") (pintype "passive+no_connect"))
    )
  )
)
